# SCH_BMS_Super_Capacitor_2022-08-26.net
KiCad netlist of a schematic drawn in EasyEDA
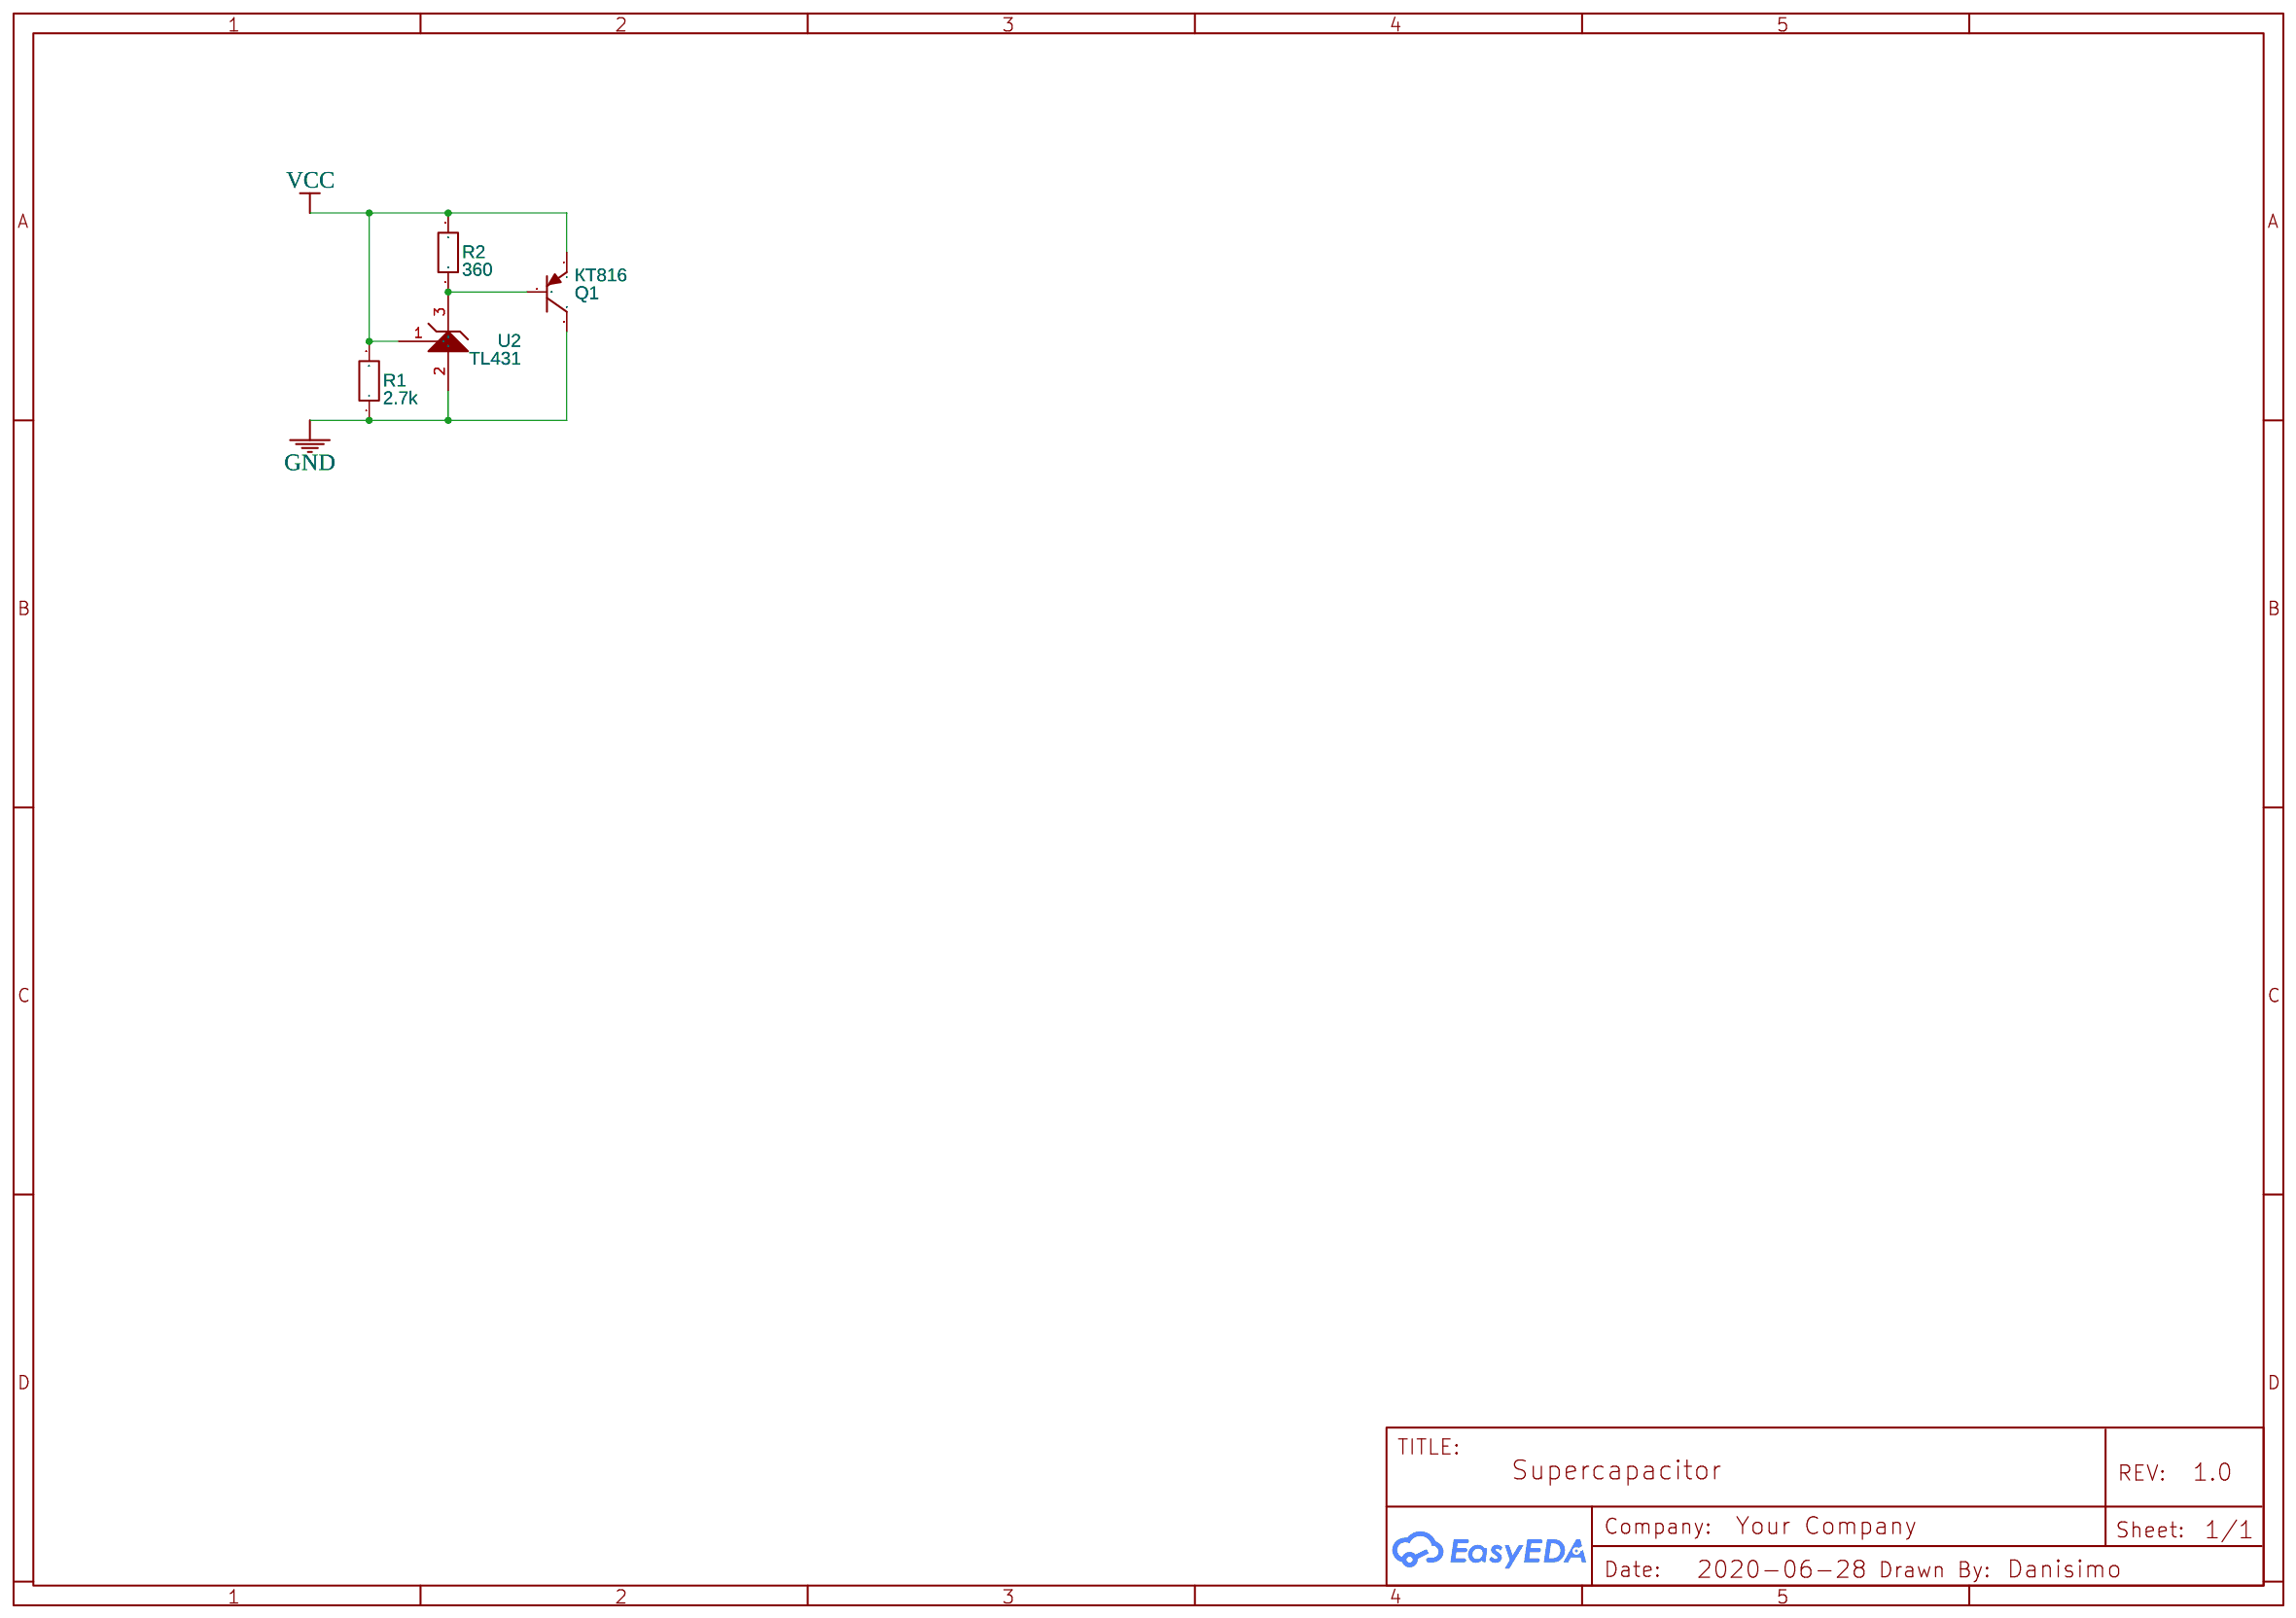
[diagram p0: schematic sheet]

(export (version "E")
  (design (tool "Eeschema 10.0.6"))
  (components
    (comp (ref "Q1") (value "КТ816") (libsource (lib "") (part "КТ816")))
    (comp (ref "R1") (value "2.7k") (libsource (lib "") (part "R_0201_EU")))
    (comp (ref "R2") (value "360") (libsource (lib "") (part "R_0201_EU")))
    (comp (ref "U2")
      (value "TL431")
      (fields (field (name "BOM_Manufacturer Part") "TL431AILP") (field (name "BOM_Supplier Part") "C72108"))
      (libsource (lib "") (part "TL431"))
    )
  )
  (nets
    (net (code "1") (name "GND") (class "Default")
      (node (ref "Q1") (pin "3") (pinfunction "C_3") (pintype "unspecified"))
      (node (ref "R1") (pin "1") (pinfunction "1_1") (pintype "unspecified"))
      (node (ref "U2") (pin "2") (pinfunction "ANODE_2") (pintype "passive"))
    )
    (net (code "2") (name "Net-(Q1-B)") (class "Default")
      (node (ref "Q1") (pin "2") (pinfunction "B_2") (pintype "unspecified"))
      (node (ref "R2") (pin "1") (pinfunction "1_1") (pintype "unspecified"))
      (node (ref "U2") (pin "3") (pinfunction "CATHODE_3") (pintype "unspecified"))
    )
    (net (code "3") (name "VCC") (class "Default")
      (node (ref "Q1") (pin "1") (pinfunction "E_1") (pintype "unspecified"))
      (node (ref "R1") (pin "2") (pinfunction "2_2") (pintype "unspecified"))
      (node (ref "R2") (pin "2") (pinfunction "2_2") (pintype "unspecified"))
      (node (ref "U2") (pin "1") (pinfunction "REF_1") (pintype "unspecified"))
    )
  )
)
